# analog_input.net
KiCad netlist of a schematic drawn in Altium Designer
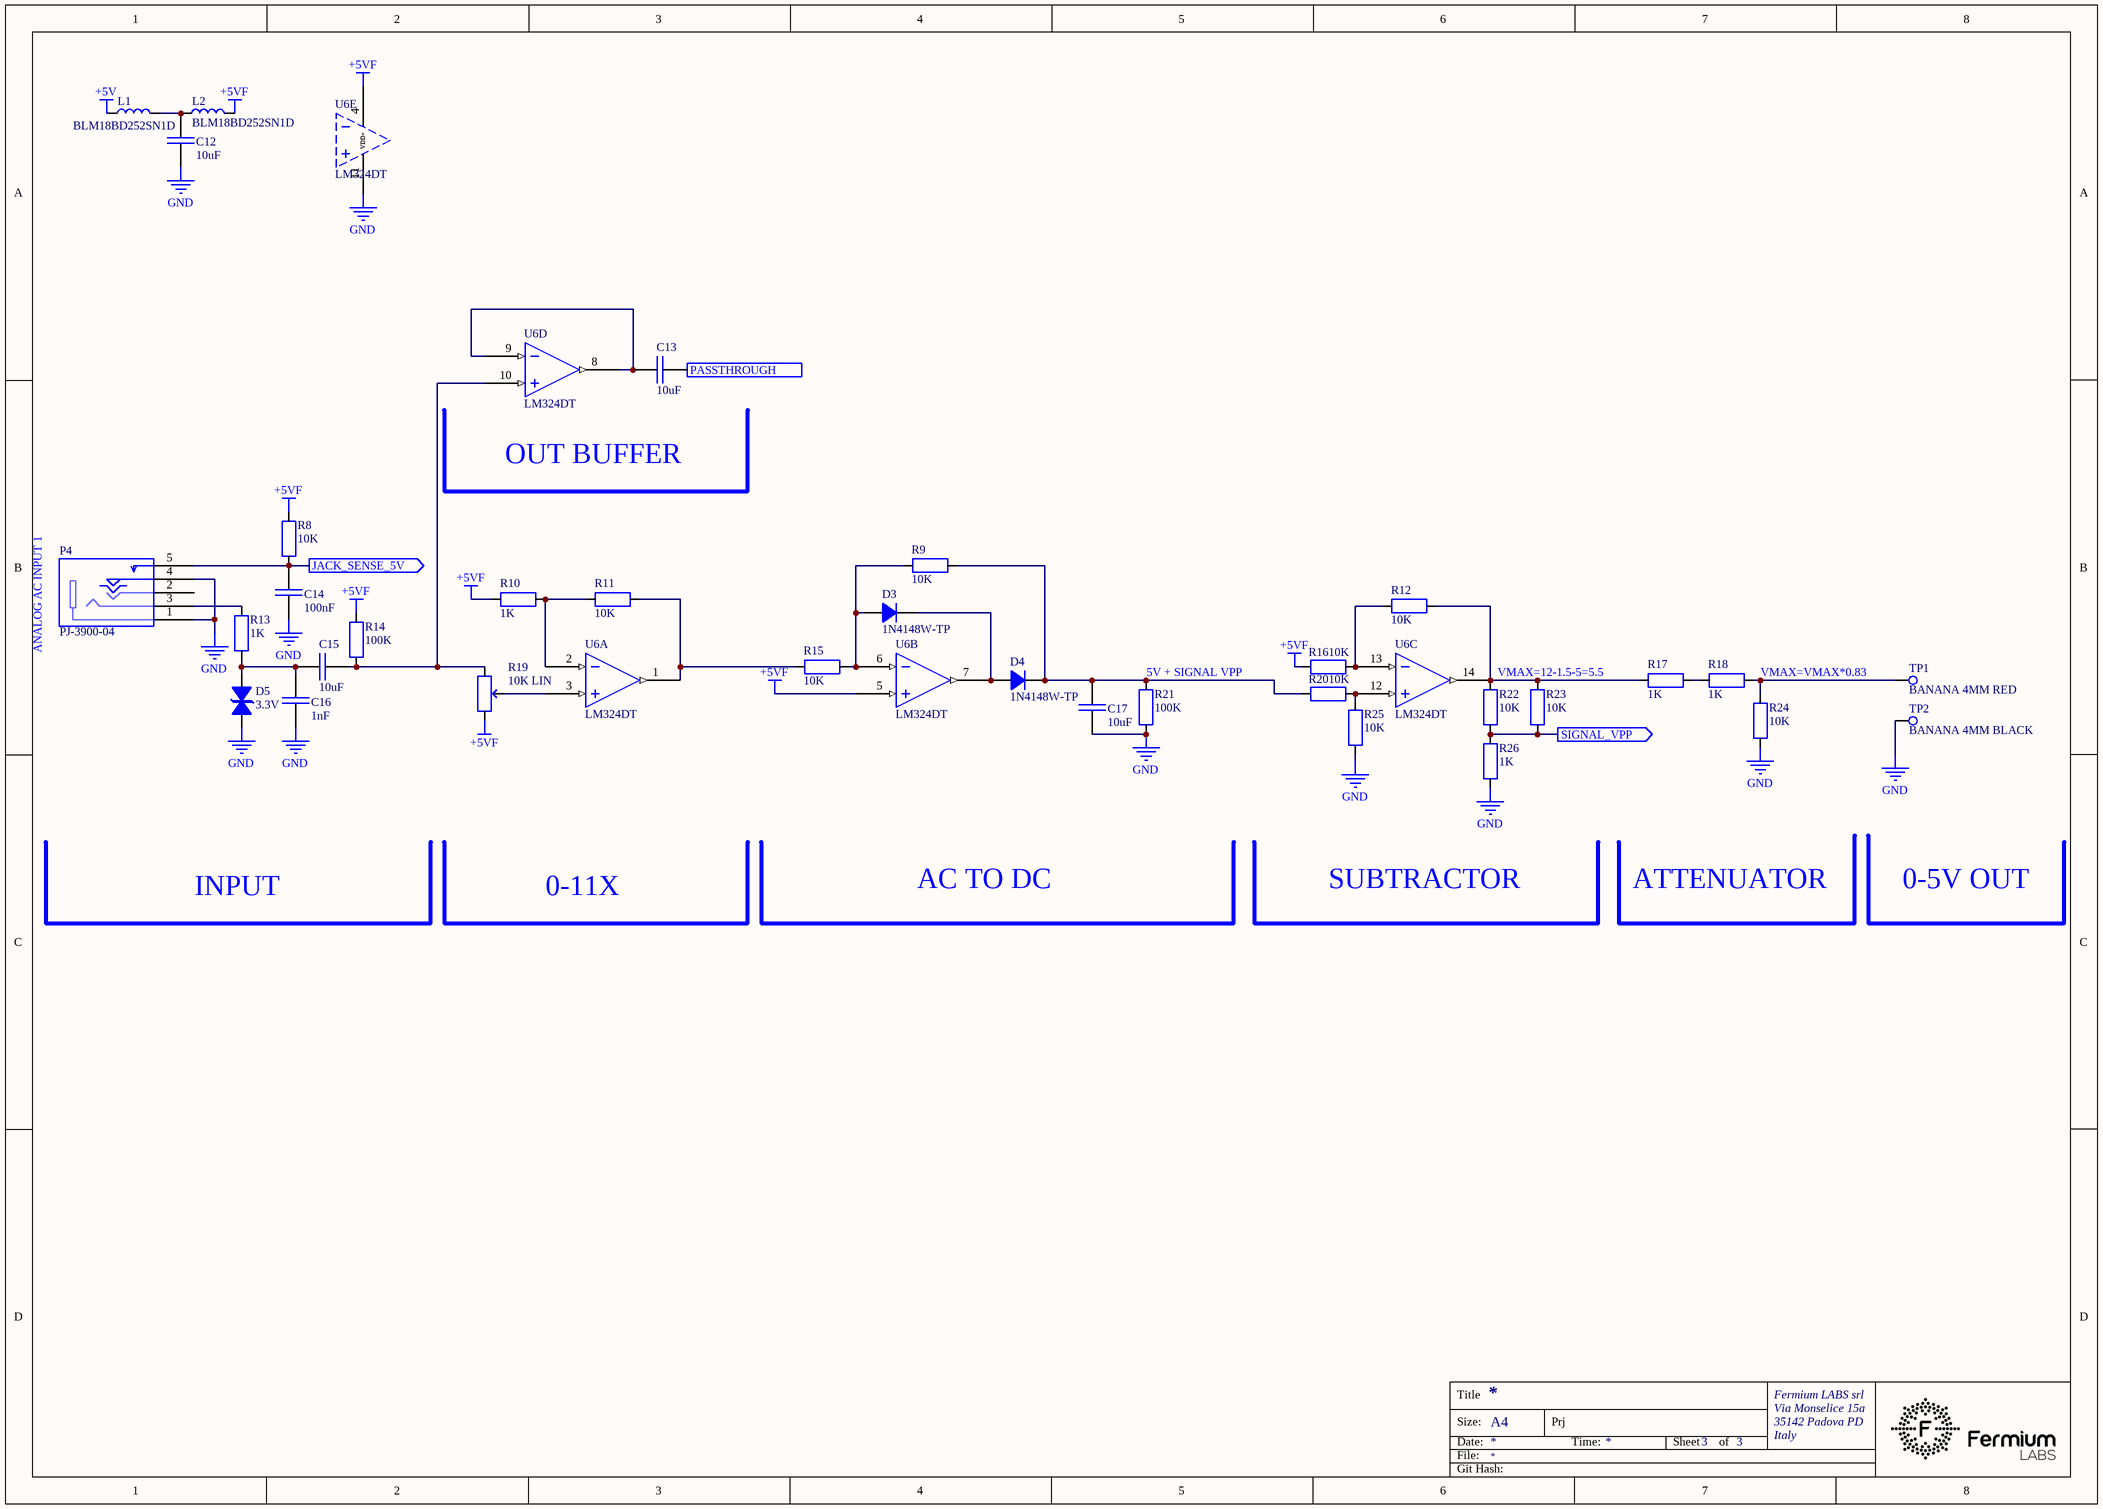
[diagram p0: analog_input.SchDoc]

(export (version "E")
  (design (tool "Eeschema 10.0.6"))
  (components
    (comp (ref "C12")
      (value "10uF")
      (footprint "CAP 0805_2012")
      (description "CAP SMD MLCC 10uF 25V 0805 X5R")
      (fields (field (name "PART NUMBER") "1ffbe5a9-0884-4740-bdad-20a6a98400e6"))
      (libsource (lib "frmdblib") (part "GENERIC_C"))
    )
    (comp (ref "C13")
      (value "10uF")
      (footprint "CAP 0805_2012")
      (description "CAP SMD MLCC 10uF 25V 0805 X5R")
      (fields (field (name "PART NUMBER") "1ffbe5a9-0884-4740-bdad-20a6a98400e6"))
      (libsource (lib "frmdblib") (part "GENERIC_C"))
    )
    (comp (ref "C14")
      (value "100nF")
      (footprint "CAP 0603_1608")
      (description "CAP SMD MLCC 100nF 25V 0603 X7R")
      (fields (field (name "PART NUMBER") "02841f84-ac15-41b5-9e17-915f8f067828"))
      (libsource (lib "frmdblib") (part "GENERIC_C"))
    )
    (comp (ref "C15")
      (value "10uF")
      (footprint "CAP 0805_2012")
      (description "CAP SMD MLCC 10uF 25V 0805 X5R")
      (fields (field (name "PART NUMBER") "1ffbe5a9-0884-4740-bdad-20a6a98400e6"))
      (libsource (lib "frmdblib") (part "GENERIC_C"))
    )
    (comp (ref "C16")
      (value "1nF")
      (footprint "CAP 0603_1608")
      (description "CAP SMD MLCC 1nF 50V 0603 X7R")
      (fields (field (name "PART NUMBER") "0eca2548-3630-4fea-a3d5-94248c1cae74"))
      (libsource (lib "frmdblib") (part "GENERIC_C"))
    )
    (comp (ref "C17")
      (value "10uF")
      (footprint "CAP 0805_2012")
      (description "CAP SMD MLCC 10uF 25V 0805 X5R")
      (fields (field (name "PART NUMBER") "1ffbe5a9-0884-4740-bdad-20a6a98400e6"))
      (libsource (lib "frmdblib") (part "GENERIC_C"))
    )
    (comp (ref "D3")
      (value "1N4148W-TP")
      (footprint "SOD-123")
      (description "DIODE SMD 100V 150mA 1.5Vf SOD-123 4148")
      (fields (field (name "PART NUMBER") "5e920700-75df-48e3-84dd-8f9f777caed8"))
      (libsource (lib "frmdblib") (part "GENERIC_D"))
    )
    (comp (ref "D4")
      (value "1N4148W-TP")
      (footprint "SOD-123")
      (description "DIODE SMD 100V 150mA 1.5Vf SOD-123 4148")
      (fields (field (name "PART NUMBER") "5e920700-75df-48e3-84dd-8f9f777caed8"))
      (libsource (lib "frmdblib") (part "GENERIC_D"))
    )
    (comp (ref "D5")
      (value "3.3V")
      (footprint "SOD523F")
      (description "DIODE SMD TVS 3.3V BIDIRECTIONAL SOD-523")
      (fields (field (name "PART NUMBER") "d6266fd0-7428-4fb9-a062-338cdce926fd"))
      (libsource (lib "frmdblib") (part "GENERIC_D_TVS_BI"))
    )
    (comp (ref "L1")
      (value "BLM18BD252SN1D")
      (footprint "FER 0603_1608")
      (description "FER SMD CHIP 0603 400mA 2.5K@100MHz 500mOhm")
      (fields (field (name "PART NUMBER") "c9e30ae8-9d5b-4135-a079-b1147da846d8"))
      (libsource (lib "frmdblib") (part "GENERIC_L"))
    )
    (comp (ref "L2")
      (value "BLM18BD252SN1D")
      (footprint "FER 0603_1608")
      (description "FER SMD CHIP 0603 400mA 2.5K@100MHz 500mOhm")
      (fields (field (name "PART NUMBER") "c9e30ae8-9d5b-4135-a079-b1147da846d8"))
      (libsource (lib "frmdblib") (part "GENERIC_L"))
    )
    (comp (ref "P4")
      (value "PJ-3900-04")
      (footprint "7EF2B92C-0FC9-4C85-B662-5CEC65BFCCC4")
      (description "CONN THT 3.5mm AUDIO STEREO AUX SWITCH")
      (fields (field (name "PART NUMBER") "80507a24-5d7c-4cf5-953e-f54832d54564"))
      (libsource (lib "frmdblib") (part "46E41D2F-79BD-46AC-B778-70B2D50A946A"))
    )
    (comp (ref "R8")
      (value "10K")
      (footprint "RES 0603_1608")
      (description "RES SMD 10K OHM 1% 1/10W 0603")
      (fields (field (name "PART NUMBER") "93242766-ba1d-462d-b58f-ce1dfc4129c8"))
      (libsource (lib "frmdblib") (part "GENERIC_R"))
    )
    (comp (ref "R9")
      (value "10K")
      (footprint "RES 0603_1608")
      (description "RES SMD 10K OHM 1% 1/10W 0603")
      (fields (field (name "PART NUMBER") "93242766-ba1d-462d-b58f-ce1dfc4129c8"))
      (libsource (lib "frmdblib") (part "GENERIC_R"))
    )
    (comp (ref "R10")
      (value "1K")
      (footprint "RES 0603_1608")
      (description "RES SMD 1K OHM 1% 1/10W 0603")
      (fields (field (name "PART NUMBER") "a678220f-9e9d-4863-a833-9993504f723c"))
      (libsource (lib "frmdblib") (part "GENERIC_R"))
    )
    (comp (ref "R11")
      (value "10K")
      (footprint "RES 0603_1608")
      (description "RES SMD 10K OHM 1% 1/10W 0603")
      (fields (field (name "PART NUMBER") "93242766-ba1d-462d-b58f-ce1dfc4129c8"))
      (libsource (lib "frmdblib") (part "GENERIC_R"))
    )
    (comp (ref "R12")
      (value "10K")
      (footprint "RES 0603_1608")
      (description "RES SMD 10K OHM 1% 1/10W 0603")
      (fields (field (name "PART NUMBER") "93242766-ba1d-462d-b58f-ce1dfc4129c8"))
      (libsource (lib "frmdblib") (part "GENERIC_R"))
    )
    (comp (ref "R13")
      (value "1K")
      (footprint "RES 0603_1608")
      (description "RES SMD 1K OHM 1% 1/10W 0603")
      (fields (field (name "PART NUMBER") "a678220f-9e9d-4863-a833-9993504f723c"))
      (libsource (lib "frmdblib") (part "GENERIC_R"))
    )
    (comp (ref "R14")
      (value "100K")
      (footprint "RES 0603_1608")
      (description "RES SMD 100K OHM 1% 1/10W 0603")
      (fields (field (name "PART NUMBER") "76af10b3-9d85-4b5c-a2d6-26cc74f432f7"))
      (libsource (lib "frmdblib") (part "GENERIC_R"))
    )
    (comp (ref "R15")
      (value "10K")
      (footprint "RES 0603_1608")
      (description "RES SMD 10K OHM 1% 1/10W 0603")
      (fields (field (name "PART NUMBER") "93242766-ba1d-462d-b58f-ce1dfc4129c8"))
      (libsource (lib "frmdblib") (part "GENERIC_R"))
    )
    (comp (ref "R16")
      (value "10K")
      (footprint "RES 0603_1608")
      (description "RES SMD 10K OHM 1% 1/10W 0603")
      (fields (field (name "PART NUMBER") "93242766-ba1d-462d-b58f-ce1dfc4129c8"))
      (libsource (lib "frmdblib") (part "GENERIC_R"))
    )
    (comp (ref "R17")
      (value "1K")
      (footprint "RES 0603_1608")
      (description "RES SMD 1K OHM 1% 1/10W 0603")
      (fields (field (name "PART NUMBER") "a678220f-9e9d-4863-a833-9993504f723c"))
      (libsource (lib "frmdblib") (part "GENERIC_R"))
    )
    (comp (ref "R18")
      (value "1K")
      (footprint "RES 0603_1608")
      (description "RES SMD 1K OHM 1% 1/10W 0603")
      (fields (field (name "PART NUMBER") "a678220f-9e9d-4863-a833-9993504f723c"))
      (libsource (lib "frmdblib") (part "GENERIC_R"))
    )
    (comp (ref "R19")
      (value "10K LIN")
      (description "POT 10K LIN")
      (fields (field (name "PART NUMBER") "3df905ea-1e80-4add-859d-a36edd7f106c"))
      (libsource (lib "frmdblib") (part "GENERIC_R_VAR"))
    )
    (comp (ref "R20")
      (value "10K")
      (footprint "RES 0603_1608")
      (description "RES SMD 10K OHM 1% 1/10W 0603")
      (fields (field (name "PART NUMBER") "93242766-ba1d-462d-b58f-ce1dfc4129c8"))
      (libsource (lib "frmdblib") (part "GENERIC_R"))
    )
    (comp (ref "R21")
      (value "100K")
      (footprint "RES 0603_1608")
      (description "RES SMD 100K OHM 1% 1/10W 0603")
      (fields (field (name "PART NUMBER") "76af10b3-9d85-4b5c-a2d6-26cc74f432f7"))
      (libsource (lib "frmdblib") (part "GENERIC_R"))
    )
    (comp (ref "R22")
      (value "10K")
      (footprint "RES 0603_1608")
      (description "RES SMD 10K OHM 1% 1/10W 0603")
      (fields (field (name "PART NUMBER") "93242766-ba1d-462d-b58f-ce1dfc4129c8"))
      (libsource (lib "frmdblib") (part "GENERIC_R"))
    )
    (comp (ref "R23")
      (value "10K")
      (footprint "RES 0603_1608")
      (description "RES SMD 10K OHM 1% 1/10W 0603")
      (fields (field (name "PART NUMBER") "93242766-ba1d-462d-b58f-ce1dfc4129c8"))
      (libsource (lib "frmdblib") (part "GENERIC_R"))
    )
    (comp (ref "R24")
      (value "10K")
      (footprint "RES 0603_1608")
      (description "RES SMD 10K OHM 1% 1/10W 0603")
      (fields (field (name "PART NUMBER") "93242766-ba1d-462d-b58f-ce1dfc4129c8"))
      (libsource (lib "frmdblib") (part "GENERIC_R"))
    )
    (comp (ref "R25")
      (value "10K")
      (footprint "RES 0603_1608")
      (description "RES SMD 10K OHM 1% 1/10W 0603")
      (fields (field (name "PART NUMBER") "93242766-ba1d-462d-b58f-ce1dfc4129c8"))
      (libsource (lib "frmdblib") (part "GENERIC_R"))
    )
    (comp (ref "R26")
      (value "1K")
      (footprint "RES 0603_1608")
      (description "RES SMD 1K OHM 1% 1/10W 0603")
      (fields (field (name "PART NUMBER") "a678220f-9e9d-4863-a833-9993504f723c"))
      (libsource (lib "frmdblib") (part "GENERIC_R"))
    )
    (comp (ref "TP1")
      (value "BANANA 4MM RED")
      (description "CONN BANANA SOCKET 4MM RED")
      (fields (field (name "PART NUMBER") "3b84d3c9-1de5-4004-b768-3958a778153b"))
      (libsource (lib "frmdblib") (part "GENERIC_TP"))
    )
    (comp (ref "TP2")
      (value "BANANA 4MM BLACK")
      (description "CONN BANANA SOCKET 4MM BLACK")
      (fields (field (name "PART NUMBER") "80ef162c-aaff-440a-80ad-5900ce15f9c1"))
      (libsource (lib "frmdblib") (part "GENERIC_TP"))
    )
    (comp (ref "U6")
      (value "LM324DT")
      (footprint "34355DA5-B1DA-47C2-A88A-ECF82120A4F7")
      (description "IC SMD OPAMP LM324DT SO-14")
      (fields (field (name "PART NUMBER") "21a85167-c328-42f7-a52e-365842c6dad3"))
      (libsource (lib "frmdblib") (part "B8DB4B19-8E9C-4F46-A390-7A352E041443"))
    )
  )
  (nets
    (net (code "1") (name "+5V") (class "Default") (node (ref "L1") (pin "1") (pintype "passive")))
    (net (code "2") (name "+5VF") (class "Default")
      (node (ref "L2") (pin "2") (pintype "passive"))
      (node (ref "R10") (pin "2") (pintype "passive"))
      (node (ref "R14") (pin "1") (pintype "passive"))
      (node (ref "R16") (pin "2") (pintype "passive"))
      (node (ref "R19") (pin "2") (pintype "passive"))
      (node (ref "R8") (pin "2") (pintype "passive"))
      (node (ref "U6") (pin "4") (pinfunction "VDD+_4") (pintype "power_in"))
      (node (ref "U6") (pin "5") (pinfunction "IN+_5") (pintype "input"))
    )
    (net (code "3") (name "/JACK_SENSE_5V") (class "Default")
      (node (ref "C14") (pin "2") (pintype "passive"))
      (node (ref "P4") (pin "5") (pinfunction "AUX_5") (pintype "passive"))
      (node (ref "R8") (pin "1") (pintype "passive"))
    )
    (net (code "4") (name "/PASSTHROUGH") (class "Default") (node (ref "C13") (pin "1") (pintype "passive")))
    (net (code "5") (name "/SIGNAL_VPP") (class "Default")
      (node (ref "R22") (pin "2") (pintype "passive"))
      (node (ref "R23") (pin "2") (pintype "passive"))
      (node (ref "R26") (pin "1") (pintype "passive"))
    )
    (net (code "6") (name "GND") (class "Default")
      (node (ref "C12") (pin "1") (pintype "passive"))
      (node (ref "C14") (pin "1") (pintype "passive"))
      (node (ref "C16") (pin "2") (pintype "passive"))
      (node (ref "C17") (pin "2") (pintype "passive"))
      (node (ref "D5") (pin "2") (pintype "passive"))
      (node (ref "P4") (pin "1") (pinfunction "GND_1") (pintype "passive"))
      (node (ref "P4") (pin "4") (pinfunction "AUX_4") (pintype "passive"))
      (node (ref "R21") (pin "1") (pintype "passive"))
      (node (ref "R24") (pin "2") (pintype "passive"))
      (node (ref "R25") (pin "2") (pintype "passive"))
      (node (ref "R26") (pin "2") (pintype "passive"))
      (node (ref "TP2") (pin "1") (pinfunction "TP_1") (pintype "passive"))
      (node (ref "U6") (pin "11") (pinfunction "VDD-_11") (pintype "power_in"))
    )
    (net (code "7") (name "Net-(C12-Pad2)") (class "Default")
      (node (ref "C12") (pin "2") (pintype "passive"))
      (node (ref "L1") (pin "2") (pintype "passive"))
      (node (ref "L2") (pin "1") (pintype "passive"))
    )
    (net (code "8") (name "Net-(C15-Pad1)") (class "Default")
      (node (ref "C15") (pin "1") (pintype "passive"))
      (node (ref "C16") (pin "1") (pintype "passive"))
      (node (ref "D5") (pin "1") (pintype "passive"))
      (node (ref "R13") (pin "1") (pintype "passive"))
    )
    (net (code "9") (name "Net-(D3-A)") (class "Default")
      (node (ref "D3") (pin "2") (pinfunction "A_2") (pintype "passive"))
      (node (ref "R15") (pin "1") (pintype "passive"))
      (node (ref "R9") (pin "2") (pintype "passive"))
      (node (ref "U6") (pin "6") (pinfunction "IN-_6") (pintype "input"))
    )
    (net (code "10") (name "Net-(D3-K)") (class "Default")
      (node (ref "D3") (pin "1") (pinfunction "K_1") (pintype "passive"))
      (node (ref "D4") (pin "2") (pinfunction "A_2") (pintype "passive"))
      (node (ref "U6") (pin "7") (pinfunction "OUT_7") (pintype "output"))
    )
    (net (code "11") (name "Net-(D4-K)") (class "Default")
      (node (ref "C17") (pin "1") (pintype "passive"))
      (node (ref "D4") (pin "1") (pinfunction "K_1") (pintype "passive"))
      (node (ref "R20") (pin "2") (pintype "passive"))
      (node (ref "R21") (pin "2") (pintype "passive"))
      (node (ref "R9") (pin "1") (pintype "passive"))
    )
    (net (code "12") (name "Net-(P4-L)") (class "Default")
      (node (ref "P4") (pin "3") (pinfunction "L_3") (pintype "passive"))
      (node (ref "R13") (pin "2") (pintype "passive"))
    )
    (net (code "13") (name "Net-(R17-Pad2)") (class "Default")
      (node (ref "R17") (pin "2") (pintype "passive"))
      (node (ref "R18") (pin "1") (pintype "passive"))
    )
    (net (code "14") (name "Net-(TP1-TP)") (class "Default")
      (node (ref "R18") (pin "2") (pintype "passive"))
      (node (ref "R24") (pin "1") (pintype "passive"))
      (node (ref "TP1") (pin "1") (pinfunction "TP_1") (pintype "passive"))
    )
    (net (code "15") (name "Net-(U6A-IN+)") (class "Default")
      (node (ref "R19") (pin "3") (pintype "passive"))
      (node (ref "U6") (pin "3") (pinfunction "IN+_3") (pintype "input"))
    )
    (net (code "16") (name "Net-(U6A-IN-)") (class "Default")
      (node (ref "R10") (pin "1") (pintype "passive"))
      (node (ref "R11") (pin "1") (pintype "passive"))
      (node (ref "U6") (pin "2") (pinfunction "IN-_2") (pintype "input"))
    )
    (net (code "17") (name "Net-(U6A-OUT)") (class "Default")
      (node (ref "R11") (pin "2") (pintype "passive"))
      (node (ref "R15") (pin "2") (pintype "passive"))
      (node (ref "U6") (pin "1") (pinfunction "OUT_1") (pintype "output"))
    )
    (net (code "18") (name "Net-(U6C-IN+)") (class "Default")
      (node (ref "R20") (pin "1") (pintype "passive"))
      (node (ref "R25") (pin "1") (pintype "passive"))
      (node (ref "U6") (pin "12") (pinfunction "IN+_12") (pintype "input"))
    )
    (net (code "19") (name "Net-(U6C-IN-)") (class "Default")
      (node (ref "R12") (pin "2") (pintype "passive"))
      (node (ref "R16") (pin "1") (pintype "passive"))
      (node (ref "U6") (pin "13") (pinfunction "IN-_13") (pintype "input"))
    )
    (net (code "20") (name "Net-(U6C-OUT)") (class "Default")
      (node (ref "R12") (pin "1") (pintype "passive"))
      (node (ref "R17") (pin "1") (pintype "passive"))
      (node (ref "R22") (pin "1") (pintype "passive"))
      (node (ref "R23") (pin "1") (pintype "passive"))
      (node (ref "U6") (pin "14") (pinfunction "OUT_14") (pintype "output"))
    )
    (net (code "21") (name "Net-(U6D-IN+)") (class "Default")
      (node (ref "C15") (pin "2") (pintype "passive"))
      (node (ref "R14") (pin "2") (pintype "passive"))
      (node (ref "R19") (pin "1") (pintype "passive"))
      (node (ref "U6") (pin "10") (pinfunction "IN+_10") (pintype "input"))
    )
    (net (code "22") (name "Net-(U6D-IN-)") (class "Default")
      (node (ref "C13") (pin "2") (pintype "passive"))
      (node (ref "U6") (pin "8") (pinfunction "OUT_8") (pintype "output"))
      (node (ref "U6") (pin "9") (pinfunction "IN-_9") (pintype "input"))
    )
    (net (code "23") (name "unconnected-(P4-R-Pad2)") (class "Default")
      (node (ref "P4") (pin "2") (pinfunction "R_2") (pintype "passive"))
    )
  )
)
